# 555LED.net
KiCad netlist of a schematic drawn in EAGLE
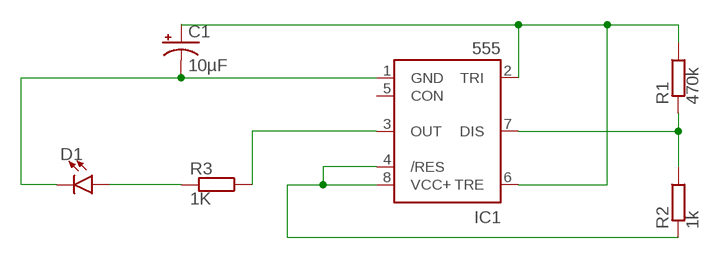
[diagram p0: schematic, sheet 1]

(export (version "E")
  (design (tool "Eeschema 10.0.6"))
  (components
    (comp (ref "C1")
      (value "10µF")
      (footprint "eagle-import:EIA6032-NOM")
      (libsource (lib "eagle-import") (part "10UF-POLAR-EIA6032-25V-10%"))
    )
    (comp (ref "D1")
      (value "LED1206")
      (footprint "eagle-import:LED-1206")
      (libsource (lib "eagle-import") (part "LED1206"))
    )
    (comp (ref "IC1")
      (value "555")
      (footprint "eagle-import:SO08")
      (libsource (lib "eagle-import") (part "555D"))
    )
    (comp (ref "R1")
      (value "470k")
      (footprint "eagle-import:BVS")
      (libsource (lib "eagle-import") (part "BVS"))
    )
    (comp (ref "R2")
      (value "1k")
      (footprint "eagle-import:BVS")
      (libsource (lib "eagle-import") (part "BVS"))
    )
    (comp (ref "R3")
      (value "1K")
      (footprint "eagle-import:BVS")
      (libsource (lib "eagle-import") (part "BVS"))
    )
  )
  (nets
    (net (code "1") (name "Net-(C1-+)") (class "Default")
      (node (ref "C1") (pin "A") (pinfunction "+_A") (pintype "passive"))
      (node (ref "IC1") (pin "2") (pinfunction "TRI_2") (pintype "input"))
      (node (ref "IC1") (pin "6") (pinfunction "TRE_6") (pintype "input"))
      (node (ref "R1") (pin "1") (pinfunction "1_1") (pintype "passive"))
    )
    (net (code "2") (name "Net-(C1--)") (class "Default")
      (node (ref "C1") (pin "C") (pinfunction "-_C") (pintype "passive"))
      (node (ref "D1") (pin "C") (pinfunction "C_C") (pintype "passive"))
      (node (ref "IC1") (pin "1") (pinfunction "GND_1") (pintype "power_in"))
    )
    (net (code "3") (name "Net-(D1-PadA)") (class "Default")
      (node (ref "D1") (pin "A") (pinfunction "A_A") (pintype "passive"))
      (node (ref "R3") (pin "2") (pinfunction "2_2") (pintype "passive"))
    )
    (net (code "4") (name "Net-(IC1-DIS)") (class "Default")
      (node (ref "IC1") (pin "7") (pinfunction "DIS_7") (pintype "input"))
      (node (ref "R1") (pin "2") (pinfunction "2_2") (pintype "passive"))
      (node (ref "R2") (pin "1") (pinfunction "1_1") (pintype "passive"))
    )
    (net (code "5") (name "Net-(IC1-OUT)") (class "Default")
      (node (ref "IC1") (pin "3") (pinfunction "OUT_3") (pintype "output"))
      (node (ref "R3") (pin "1") (pinfunction "1_1") (pintype "passive"))
    )
    (net (code "6") (name "Net-(IC1-VCC+)") (class "Default")
      (node (ref "IC1") (pin "4") (pinfunction "/RES_4") (pintype "input"))
      (node (ref "IC1") (pin "8") (pinfunction "VCC+_8") (pintype "power_in"))
      (node (ref "R2") (pin "2") (pinfunction "2_2") (pintype "passive"))
    )
    (net (code "7") (name "unconnected-(IC1-CON-Pad5)") (class "Default")
      (node (ref "IC1") (pin "5") (pinfunction "CON_5") (pintype "input"))
    )
  )
)
